# CPCIS_PWR_MOD_DC.net
KiCad netlist of a schematic drawn in Altium Designer
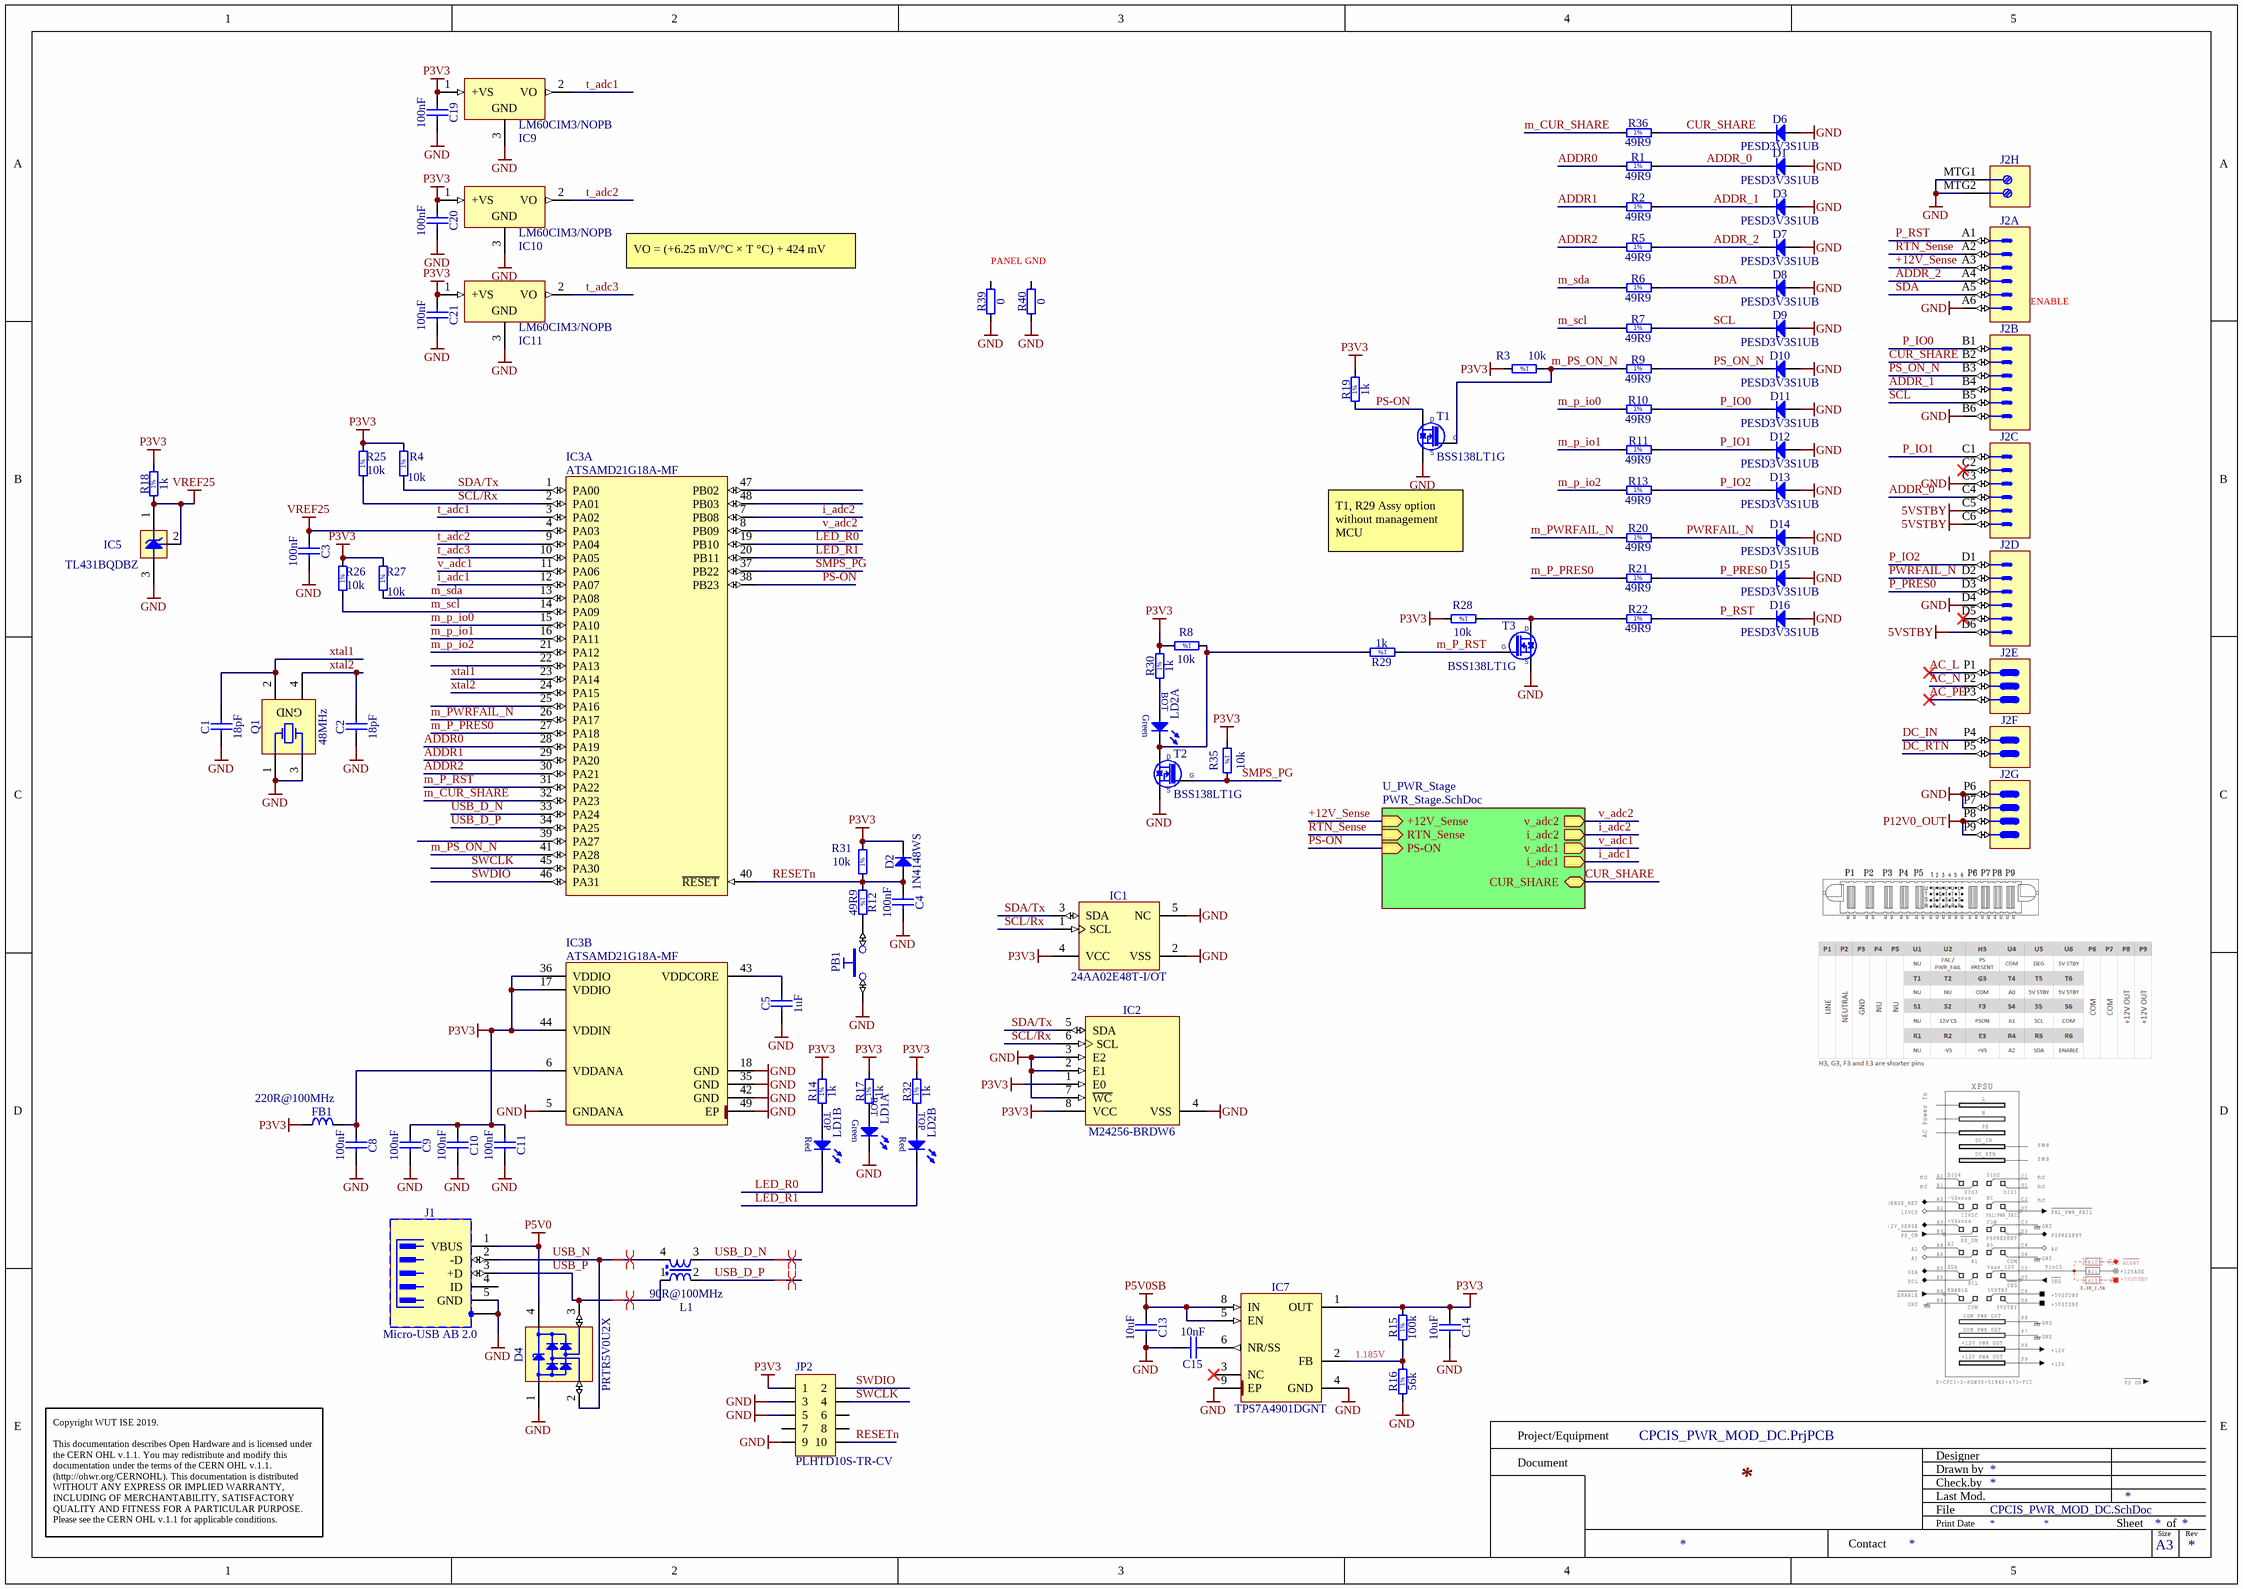
[diagram p0: CPCIS_PWR_MOD_DC.SchDoc]

(export (version "E")
  (design (tool "Eeschema 10.0.6"))
  (components
    (comp (ref "C1")
      (value "18pF")
      (footprint "CAPC1005X55N")
      (description "Non-polarised capacitor")
      (fields (field (name "PART NUMBER") "CC0402_18PF_50V_5%_C0G") (field (name "VOLTAGE") "50V"))
      (libsource (lib "Capacitors") (part "Capacitor - non polarized"))
    )
    (comp (ref "C2")
      (value "18pF")
      (footprint "CAPC1005X55N")
      (description "Non-polarised capacitor")
      (fields (field (name "PART NUMBER") "CC0402_18PF_50V_5%_C0G") (field (name "VOLTAGE") "50V"))
      (libsource (lib "Capacitors") (part "Capacitor - non polarized"))
    )
    (comp (ref "C3")
      (value "100nF")
      (footprint "CAPC1005X55N")
      (description "Non-polarised capacitor")
      (fields (field (name "PART NUMBER") "CC0402_100NF_16V_10%_X7R") (field (name "VOLTAGE") "16V"))
      (libsource (lib "Capacitors") (part "Capacitor - non polarized"))
    )
    (comp (ref "C4")
      (value "100nF")
      (footprint "CAPC1005X55N")
      (description "Non-polarised capacitor")
      (fields (field (name "PART NUMBER") "CC0402_100NF_16V_10%_X7R") (field (name "VOLTAGE") "16V"))
      (libsource (lib "Capacitors") (part "Capacitor - non polarized"))
    )
    (comp (ref "C5")
      (value "1uF")
      (footprint "CAPC1608X87N")
      (description "Non-polarised capacitor")
      (fields (field (name "PART NUMBER") "CC0603_1UF_16V_10%_X7R") (field (name "VOLTAGE") "16V"))
      (libsource (lib "Capacitors") (part "Capacitor - non polarized"))
    )
    (comp (ref "C8")
      (value "100nF")
      (footprint "CAPC1005X55N")
      (description "Non-polarised capacitor")
      (fields (field (name "PART NUMBER") "CC0402_100NF_16V_10%_X7R") (field (name "VOLTAGE") "16V"))
      (libsource (lib "Capacitors") (part "Capacitor - non polarized"))
    )
    (comp (ref "C9")
      (value "100nF")
      (footprint "CAPC1005X55N")
      (description "Non-polarised capacitor")
      (fields (field (name "PART NUMBER") "CC0402_100NF_16V_10%_X7R") (field (name "VOLTAGE") "16V"))
      (libsource (lib "Capacitors") (part "Capacitor - non polarized"))
    )
    (comp (ref "C10")
      (value "100nF")
      (footprint "CAPC1005X55N")
      (description "Non-polarised capacitor")
      (fields (field (name "PART NUMBER") "CC0402_100NF_16V_10%_X7R") (field (name "VOLTAGE") "16V"))
      (libsource (lib "Capacitors") (part "Capacitor - non polarized"))
    )
    (comp (ref "C11")
      (value "100nF")
      (footprint "CAPC1005X55N")
      (description "Non-polarised capacitor")
      (fields (field (name "PART NUMBER") "CC0402_100NF_16V_10%_X7R") (field (name "VOLTAGE") "16V"))
      (libsource (lib "Capacitors") (part "Capacitor - non polarized"))
    )
    (comp (ref "C13")
      (value "10uF")
      (footprint "CAPC2012X135N")
      (description "Non-polarised capacitor")
      (fields (field (name "PART NUMBER") "CC0805_10UF_16V_10%_X5R") (field (name "VOLTAGE") "16V"))
      (libsource (lib "Capacitors") (part "Capacitor - non polarized"))
    )
    (comp (ref "C14")
      (value "10uF")
      (footprint "CAPC2012X135N")
      (description "Non-polarised capacitor")
      (fields (field (name "PART NUMBER") "CC0805_10UF_16V_10%_X5R") (field (name "VOLTAGE") "16V"))
      (libsource (lib "Capacitors") (part "Capacitor - non polarized"))
    )
    (comp (ref "C15")
      (value "10nF")
      (footprint "CAPC1005X55N")
      (description "Non-polarised capacitor")
      (fields (field (name "PART NUMBER") "CC0402_10NF_50V_10%_X7R") (field (name "VOLTAGE") "50V"))
      (libsource (lib "Capacitors") (part "Capacitor - non polarized"))
    )
    (comp (ref "C19")
      (value "100nF")
      (footprint "CAPC1005X55N")
      (description "Non-polarised capacitor")
      (fields (field (name "PART NUMBER") "CC0402_100NF_16V_10%_X7R") (field (name "VOLTAGE") "16V"))
      (libsource (lib "Capacitors") (part "Capacitor - non polarized"))
    )
    (comp (ref "C20")
      (value "100nF")
      (footprint "CAPC1005X55N")
      (description "Non-polarised capacitor")
      (fields (field (name "PART NUMBER") "CC0402_100NF_16V_10%_X7R") (field (name "VOLTAGE") "16V"))
      (libsource (lib "Capacitors") (part "Capacitor - non polarized"))
    )
    (comp (ref "C21")
      (value "100nF")
      (footprint "CAPC1005X55N")
      (description "Non-polarised capacitor")
      (fields (field (name "PART NUMBER") "CC0402_100NF_16V_10%_X7R") (field (name "VOLTAGE") "16V"))
      (libsource (lib "Capacitors") (part "Capacitor - non polarized"))
    )
    (comp (ref "D1")
      (value "PESD3V3S1UB")
      (footprint "SODFL1608X65N")
      (description "ESD protection diode")
      (fields (field (name "VOLTAGE") "3V3") (field (name "POWER") "330W"))
      (libsource (lib "ICs And Semiconductors") (part "Diode ESD"))
    )
    (comp (ref "D2")
      (value "1N4148WS")
      (footprint "SODFL2512X100N")
      (description "Diode")
      (fields (field (name "VOLTAGE") "75V") (field (name "POWER") "150mA"))
      (libsource (lib "ICs And Semiconductors") (part "Diode"))
    )
    (comp (ref "D3")
      (value "PESD3V3S1UB")
      (footprint "SODFL1608X65N")
      (description "ESD protection diode")
      (fields (field (name "VOLTAGE") "3V3") (field (name "POWER") "330W"))
      (libsource (lib "ICs And Semiconductors") (part "Diode ESD"))
    )
    (comp (ref "D4")
      (value "PRTR5V0U2X")
      (footprint "SOT190P230X110-4N")
      (description "Ultra Low Capacitance Double Rail-to-Rail ESD Protection Diode")
      (fields (field (name "VOLTAGE") "5.5V") (field (name "MANUFACTURER") "NXP SEMICONDUCTORS"))
      (libsource (lib "ICs And Semiconductors") (part "PRTR5V0U2X"))
    )
    (comp (ref "D6")
      (value "PESD3V3S1UB")
      (footprint "SODFL1608X65N")
      (description "ESD protection diode")
      (fields (field (name "VOLTAGE") "3V3") (field (name "POWER") "330W"))
      (libsource (lib "ICs And Semiconductors") (part "Diode ESD"))
    )
    (comp (ref "D7")
      (value "PESD3V3S1UB")
      (footprint "SODFL1608X65N")
      (description "ESD protection diode")
      (fields (field (name "VOLTAGE") "3V3") (field (name "POWER") "330W"))
      (libsource (lib "ICs And Semiconductors") (part "Diode ESD"))
    )
    (comp (ref "D8")
      (value "PESD3V3S1UB")
      (footprint "SODFL1608X65N")
      (description "ESD protection diode")
      (fields (field (name "VOLTAGE") "3V3") (field (name "POWER") "330W"))
      (libsource (lib "ICs And Semiconductors") (part "Diode ESD"))
    )
    (comp (ref "D9")
      (value "PESD3V3S1UB")
      (footprint "SODFL1608X65N")
      (description "ESD protection diode")
      (fields (field (name "VOLTAGE") "3V3") (field (name "POWER") "330W"))
      (libsource (lib "ICs And Semiconductors") (part "Diode ESD"))
    )
    (comp (ref "D10")
      (value "PESD3V3S1UB")
      (footprint "SODFL1608X65N")
      (description "ESD protection diode")
      (fields (field (name "VOLTAGE") "3V3") (field (name "POWER") "330W"))
      (libsource (lib "ICs And Semiconductors") (part "Diode ESD"))
    )
    (comp (ref "D11")
      (value "PESD3V3S1UB")
      (footprint "SODFL1608X65N")
      (description "ESD protection diode")
      (fields (field (name "VOLTAGE") "3V3") (field (name "POWER") "330W"))
      (libsource (lib "ICs And Semiconductors") (part "Diode ESD"))
    )
    (comp (ref "D12")
      (value "PESD3V3S1UB")
      (footprint "SODFL1608X65N")
      (description "ESD protection diode")
      (fields (field (name "VOLTAGE") "3V3") (field (name "POWER") "330W"))
      (libsource (lib "ICs And Semiconductors") (part "Diode ESD"))
    )
    (comp (ref "D13")
      (value "PESD3V3S1UB")
      (footprint "SODFL1608X65N")
      (description "ESD protection diode")
      (fields (field (name "VOLTAGE") "3V3") (field (name "POWER") "330W"))
      (libsource (lib "ICs And Semiconductors") (part "Diode ESD"))
    )
    (comp (ref "D14")
      (value "PESD3V3S1UB")
      (footprint "SODFL1608X65N")
      (description "ESD protection diode")
      (fields (field (name "VOLTAGE") "3V3") (field (name "POWER") "330W"))
      (libsource (lib "ICs And Semiconductors") (part "Diode ESD"))
    )
    (comp (ref "D15")
      (value "PESD3V3S1UB")
      (footprint "SODFL1608X65N")
      (description "ESD protection diode")
      (fields (field (name "VOLTAGE") "3V3") (field (name "POWER") "330W"))
      (libsource (lib "ICs And Semiconductors") (part "Diode ESD"))
    )
    (comp (ref "D16")
      (value "PESD3V3S1UB")
      (footprint "SODFL1608X65N")
      (description "ESD protection diode")
      (fields (field (name "VOLTAGE") "3V3") (field (name "POWER") "330W"))
      (libsource (lib "ICs And Semiconductors") (part "Diode ESD"))
    )
    (comp (ref "FB1")
      (value "220R@100MHz")
      (footprint "INDC2012X105N")
      (description "Inductor")
      (fields (field (name "PART NUMBER") "IND0805_MURATA_BLM21PG221SN1D") (field (name "POWER") "2A"))
      (libsource (lib "Inductors & Transformers") (part "Inductor"))
    )
    (comp (ref "IC1")
      (value "24AA02E48T-I/OT")
      (footprint "SOT95P280X145-5N")
      (description "1.7V-5.5V, 2K I2C Serial EEPROM With EUI-48 Node Identity")
      (fields (field (name "MANUFACTURER") "MICROCHIP TECHNOLOGY"))
      (libsource (lib "ICs And Semiconductors") (part "24AA02E48T-I/OT"))
    )
    (comp (ref "IC2")
      (value "M24256-BRDW6")
      (footprint "SOP65P640X120-8N")
      (description "256-Kbit Serial I²C Bus EEPROM")
      (fields
        (field (name "PART NUMBER") "M24256-BRDW6P")
        (field (name "MANUFACTURER") "ST MICROELECTRONICS")
      )
      (libsource (lib "LIBRARY_SCH") (part "MEM_M24256-BRDW6P"))
    )
    (comp (ref "IC3")
      (value "ATSAMD21G18A-MF")
      (footprint "QFN50P700X700X100-49N-S525")
      (fields (field (name "MANUFACTURER") "MICROCHIP"))
      (libsource (lib "ICs And Semiconductors") (part "ATSAMD21G18A-MF"))
    )
    (comp (ref "IC5")
      (value "TL431BQDBZ")
      (footprint "SOT95P250X110-3N")
      (description "Precision Reference 1=Cathode 2=Adj 3=Anode")
      (fields (field (name "MANUFACTURER") "NXP SEMICONDUCTORS"))
      (libsource (lib "ICs And Semiconductors") (part "VREF 1C-2ADJ-3A"))
    )
    (comp (ref "IC7")
      (value "TPS7A4901DGNT")
      (footprint "SOP65P490X110-9N-R157X189")
      (description "+36V, +150mA, Ultralow-Noise, Positive Linear Regulator")
      (fields (field (name "MANUFACTURER") "TEXAS INSTRUMENTS"))
      (libsource (lib "ICs And Semiconductors") (part "TPS7A4901DGN"))
    )
    (comp (ref "IC9")
      (value "LM60CIM3/NOPB")
      (footprint "DBZ0003A_M")
      (description "2.7V Temperature Sensor, 3-pin SOT-23, Pb-Free")
      (fields (field (name "MANUFACTURER") "Texas Instruments"))
      (libsource (lib "Altium Content Vault") (part "SEN-TEMP-LM34AH-3"))
    )
    (comp (ref "IC10")
      (value "LM60CIM3/NOPB")
      (footprint "DBZ0003A_M")
      (description "2.7V Temperature Sensor, 3-pin SOT-23, Pb-Free")
      (fields (field (name "MANUFACTURER") "Texas Instruments"))
      (libsource (lib "Altium Content Vault") (part "SEN-TEMP-LM34AH-3"))
    )
    (comp (ref "IC11")
      (value "LM60CIM3/NOPB")
      (footprint "DBZ0003A_M")
      (description "2.7V Temperature Sensor, 3-pin SOT-23, Pb-Free")
      (fields (field (name "MANUFACTURER") "Texas Instruments"))
      (libsource (lib "Altium Content Vault") (part "SEN-TEMP-LM34AH-3"))
    )
    (comp (ref "J1")
      (value "Micro-USB AB 2.0")
      (footprint "HIROSE_ZX62RD-AB-5P8(30)")
      (description "5 Pin + 1 Shield USB Receptacle")
      (fields
        (field (name "PART NUMBER") "HIROSE_ZX62RD-AB-5P8(30)")
        (field (name "MANUFACTURER") "HIROSE (HRS)")
      )
      (libsource (lib "Connectors") (part "Connector USB 5 Pin + 1Shield"))
    )
    (comp (ref "J2")
      (value "PwrBlade")
      (footprint "AMPHENOL_51939-667")
      (description "Thru-Hole, Lead 3.43mm, PowerBlade Right Angled Power Connector 3ACP 2P 24S 4P Contacts")
      (fields (field (name "PART NUMBER") "AMPHENOL_51939-667") (field (name "MANUFACTURER") "AMPHENOL"))
      (libsource (lib "Connectors") (part "AMPHENOL_51939-667"))
    )
    (comp (ref "JP2")
      (value "PLHTD10S-TR-CV")
      (footprint "PLHTD10S-TR-CV")
      (description "1.27 mm dual row goldpin (Maritex)")
      (libsource (lib "LIBRARY_SCH") (part "CON_2x5 1.27 SMT Male"))
    )
    (comp (ref "L1")
      (value "90R@100MHz")
      (footprint "IND_MURATA_DLW21S")
      (description "Inductor Common Mode")
      (fields (field (name "PART NUMBER") "IND_MURATA_DLW21SN900SQ2L") (field (name "POWER") "330mA"))
      (libsource (lib "Inductors & Transformers") (part "Inductor Common Mode 1Dot-2 4Dot-3"))
    )
    (comp (ref "LD1")
      (value "Red/Green")
      (footprint "LED_DIALIGHT_571-0112F")
      (description "2x LED  Botom Green, Top Red")
      (fields (field (name "PART NUMBER") "LED_DIALIGHT_571-0112F") (field (name "MANUFACTURER") "DIALIGHT"))
      (libsource (lib "ICs And Semiconductors") (part "LED x2 G-1C2A-BOT_R-3C4A-TOP"))
    )
    (comp (ref "LD2")
      (value "Red/Green")
      (footprint "LED_DIALIGHT_571-0112F")
      (description "2x LED  Botom Green, Top Red")
      (fields (field (name "PART NUMBER") "LED_DIALIGHT_571-0112F") (field (name "MANUFACTURER") "DIALIGHT"))
      (libsource (lib "ICs And Semiconductors") (part "LED x2 G-1C2A-BOT_R-3C4A-TOP"))
    )
    (comp (ref "PB1")
      (value "Push Button")
      (footprint "PB_TYCO_FSMSM")
      (description "Push-Button Switch SPDT")
      (fields (field (name "PART NUMBER") "PB_TYCO_FSMSM") (field (name "MANUFACTURER") "TYCO ELECTRONICS"))
      (libsource (lib "Eletro-mechanical") (part "PB SPST 1NO-2NO"))
    )
    (comp (ref "Q1")
      (value "48MHz")
      (footprint "XTAL_TXC_7M")
      (description "Crystal 4 pins 1=XTAL Control 2=GND3=XTAL 4=GND")
      (fields
        (field (name "PART NUMBER") "XTAL_48MHZ_TXC_7M-48.000MAHV")
        (field (name "MANUFACTURER") "TXC CORPORATION")
      )
      (libsource (lib "ICs And Semiconductors") (part "Quartz Crystal 1X 2GND 3X 4GND"))
    )
    (comp (ref "R1")
      (value "49R9")
      (footprint "RESC1005X40N")
      (description "Resistor - 1%")
      (fields (field (name "PART NUMBER") "R0402_49R9_1%_0.0625W_100PPM") (field (name "POWER") "0.0625W"))
      (libsource (lib "Resistors") (part "Resistor - 1%"))
    )
    (comp (ref "R2")
      (value "49R9")
      (footprint "RESC1005X40N")
      (description "Resistor - 1%")
      (fields (field (name "PART NUMBER") "R0402_49R9_1%_0.0625W_100PPM") (field (name "POWER") "0.0625W"))
      (libsource (lib "Resistors") (part "Resistor - 1%"))
    )
    (comp (ref "R3")
      (value "10k")
      (footprint "RESC1005X40N")
      (description "Resistor - 1%")
      (fields (field (name "PART NUMBER") "R0402_10K_1%_0.0625W_100PPM") (field (name "POWER") "0.0625W"))
      (libsource (lib "Resistors") (part "Resistor - 1%"))
    )
    (comp (ref "R4")
      (value "10k")
      (footprint "RESC1005X40N")
      (description "Resistor - 1%")
      (fields (field (name "PART NUMBER") "R0402_10K_1%_0.0625W_100PPM") (field (name "POWER") "0.0625W"))
      (libsource (lib "Resistors") (part "Resistor - 1%"))
    )
    (comp (ref "R5")
      (value "49R9")
      (footprint "RESC1005X40N")
      (description "Resistor - 1%")
      (fields (field (name "PART NUMBER") "R0402_49R9_1%_0.0625W_100PPM") (field (name "POWER") "0.0625W"))
      (libsource (lib "Resistors") (part "Resistor - 1%"))
    )
    (comp (ref "R6")
      (value "49R9")
      (footprint "RESC1005X40N")
      (description "Resistor - 1%")
      (fields (field (name "PART NUMBER") "R0402_49R9_1%_0.0625W_100PPM") (field (name "POWER") "0.0625W"))
      (libsource (lib "Resistors") (part "Resistor - 1%"))
    )
    (comp (ref "R7")
      (value "49R9")
      (footprint "RESC1005X40N")
      (description "Resistor - 1%")
      (fields (field (name "PART NUMBER") "R0402_49R9_1%_0.0625W_100PPM") (field (name "POWER") "0.0625W"))
      (libsource (lib "Resistors") (part "Resistor - 1%"))
    )
    (comp (ref "R8")
      (value "10k")
      (footprint "RESC1005X40N")
      (description "Resistor - 1%")
      (fields (field (name "PART NUMBER") "R0402_10K_1%_0.0625W_100PPM") (field (name "POWER") "0.0625W"))
      (libsource (lib "Resistors") (part "Resistor - 1%"))
    )
    (comp (ref "R9")
      (value "49R9")
      (footprint "RESC1005X40N")
      (description "Resistor - 1%")
      (fields (field (name "PART NUMBER") "R0402_49R9_1%_0.0625W_100PPM") (field (name "POWER") "0.0625W"))
      (libsource (lib "Resistors") (part "Resistor - 1%"))
    )
    (comp (ref "R10")
      (value "49R9")
      (footprint "RESC1005X40N")
      (description "Resistor - 1%")
      (fields (field (name "PART NUMBER") "R0402_49R9_1%_0.0625W_100PPM") (field (name "POWER") "0.0625W"))
      (libsource (lib "Resistors") (part "Resistor - 1%"))
    )
    (comp (ref "R11")
      (value "49R9")
      (footprint "RESC1005X40N")
      (description "Resistor - 1%")
      (fields (field (name "PART NUMBER") "R0402_49R9_1%_0.0625W_100PPM") (field (name "POWER") "0.0625W"))
      (libsource (lib "Resistors") (part "Resistor - 1%"))
    )
    (comp (ref "R12")
      (value "49R9")
      (footprint "RESC1005X40N")
      (description "Resistor - 1%")
      (fields (field (name "PART NUMBER") "R0402_49R9_1%_0.0625W_100PPM") (field (name "POWER") "0.0625W"))
      (libsource (lib "Resistors") (part "Resistor - 1%"))
    )
    (comp (ref "R13")
      (value "49R9")
      (footprint "RESC1005X40N")
      (description "Resistor - 1%")
      (fields (field (name "PART NUMBER") "R0402_49R9_1%_0.0625W_100PPM") (field (name "POWER") "0.0625W"))
      (libsource (lib "Resistors") (part "Resistor - 1%"))
    )
    (comp (ref "R14")
      (value "1k")
      (footprint "RESC1005X40N")
      (description "Resistor - 1%")
      (fields (field (name "PART NUMBER") "R0402_1K_1%_0.0625W_100PPM") (field (name "POWER") "0.0625W"))
      (libsource (lib "Resistors") (part "Resistor - 1%"))
    )
    (comp (ref "R15")
      (value "100k")
      (footprint "RESC1005X40N")
      (description "Resistor - 1%")
      (fields (field (name "PART NUMBER") "R0402_100K_1%_0.0625W_100PPM") (field (name "POWER") "0.0625W"))
      (libsource (lib "Resistors") (part "Resistor - 1%"))
    )
    (comp (ref "R16")
      (value "56k")
      (footprint "RESC1005X40N")
      (description "Resistor - 1%")
      (fields (field (name "PART NUMBER") "R0402_56K_1%_0.0625W_100PPM") (field (name "POWER") "0.0625W"))
      (libsource (lib "Resistors") (part "Resistor - 1%"))
    )
    (comp (ref "R17")
      (value "1k")
      (footprint "RESC1005X40N")
      (description "Resistor - 1%")
      (fields (field (name "PART NUMBER") "R0402_1K_1%_0.0625W_100PPM") (field (name "POWER") "0.0625W"))
      (libsource (lib "Resistors") (part "Resistor - 1%"))
    )
    (comp (ref "R18")
      (value "1k")
      (footprint "RESC1005X40N")
      (description "Resistor - 1%")
      (fields (field (name "PART NUMBER") "R0402_1K_1%_0.0625W_100PPM") (field (name "POWER") "0.0625W"))
      (libsource (lib "Resistors") (part "Resistor - 1%"))
    )
    (comp (ref "R19")
      (value "1k")
      (footprint "RESC1005X40N")
      (description "Resistor - 1%")
      (fields (field (name "PART NUMBER") "R0402_1K_1%_0.0625W_100PPM") (field (name "POWER") "0.0625W"))
      (libsource (lib "Resistors") (part "Resistor - 1%"))
    )
    (comp (ref "R20")
      (value "49R9")
      (footprint "RESC1005X40N")
      (description "Resistor - 1%")
      (fields (field (name "PART NUMBER") "R0402_49R9_1%_0.0625W_100PPM") (field (name "POWER") "0.0625W"))
      (libsource (lib "Resistors") (part "Resistor - 1%"))
    )
    (comp (ref "R21")
      (value "49R9")
      (footprint "RESC1005X40N")
      (description "Resistor - 1%")
      (fields (field (name "PART NUMBER") "R0402_49R9_1%_0.0625W_100PPM") (field (name "POWER") "0.0625W"))
      (libsource (lib "Resistors") (part "Resistor - 1%"))
    )
    (comp (ref "R22")
      (value "49R9")
      (footprint "RESC1005X40N")
      (description "Resistor - 1%")
      (fields (field (name "PART NUMBER") "R0402_49R9_1%_0.0625W_100PPM") (field (name "POWER") "0.0625W"))
      (libsource (lib "Resistors") (part "Resistor - 1%"))
    )
    (comp (ref "R25")
      (value "10k")
      (footprint "RESC1005X40N")
      (description "Resistor - 1%")
      (fields (field (name "PART NUMBER") "R0402_10K_1%_0.0625W_100PPM") (field (name "POWER") "0.0625W"))
      (libsource (lib "Resistors") (part "Resistor - 1%"))
    )
    (comp (ref "R26")
      (value "10k")
      (footprint "RESC1005X40N")
      (description "Resistor - 1%")
      (fields (field (name "PART NUMBER") "R0402_10K_1%_0.0625W_100PPM") (field (name "POWER") "0.0625W"))
      (libsource (lib "Resistors") (part "Resistor - 1%"))
    )
    (comp (ref "R27")
      (value "10k")
      (footprint "RESC1005X40N")
      (description "Resistor - 1%")
      (fields (field (name "PART NUMBER") "R0402_10K_1%_0.0625W_100PPM") (field (name "POWER") "0.0625W"))
      (libsource (lib "Resistors") (part "Resistor - 1%"))
    )
    (comp (ref "R28")
      (value "10k")
      (footprint "RESC1005X40N")
      (description "Resistor - 1%")
      (fields (field (name "PART NUMBER") "R0402_10K_1%_0.0625W_100PPM") (field (name "POWER") "0.0625W"))
      (libsource (lib "Resistors") (part "Resistor - 1%"))
    )
    (comp (ref "R29")
      (value "1k")
      (footprint "RESC1005X40N")
      (description "Resistor - 1%")
      (fields (field (name "PART NUMBER") "R0402_1K_1%_0.0625W_100PPM") (field (name "POWER") "0.0625W"))
      (libsource (lib "Resistors") (part "Resistor - 1%"))
    )
    (comp (ref "R30")
      (value "1k")
      (footprint "RESC1005X40N")
      (description "Resistor - 1%")
      (fields (field (name "PART NUMBER") "R0402_1K_1%_0.0625W_100PPM") (field (name "POWER") "0.0625W"))
      (libsource (lib "Resistors") (part "Resistor - 1%"))
    )
    (comp (ref "R31")
      (value "10k")
      (footprint "RESC1005X40N")
      (description "Resistor - 1%")
      (fields (field (name "PART NUMBER") "R0402_10K_1%_0.0625W_100PPM") (field (name "POWER") "0.0625W"))
      (libsource (lib "Resistors") (part "Resistor - 1%"))
    )
    (comp (ref "R32")
      (value "1k")
      (footprint "RESC1005X40N")
      (description "Resistor - 1%")
      (fields (field (name "PART NUMBER") "R0402_1K_1%_0.0625W_100PPM") (field (name "POWER") "0.0625W"))
      (libsource (lib "Resistors") (part "Resistor - 1%"))
    )
    (comp (ref "R35")
      (value "10k")
      (footprint "RESC1005X40N")
      (description "Resistor - 1%")
      (fields (field (name "PART NUMBER") "R0402_10K_1%_0.0625W_100PPM") (field (name "POWER") "0.0625W"))
      (libsource (lib "Resistors") (part "Resistor - 1%"))
    )
    (comp (ref "R36")
      (value "49R9")
      (footprint "RESC1005X40N")
      (description "Resistor - 1%")
      (fields (field (name "PART NUMBER") "R0402_49R9_1%_0.0625W_100PPM") (field (name "POWER") "0.0625W"))
      (libsource (lib "Resistors") (part "Resistor - 1%"))
    )
    (comp (ref "R39")
      (value "0")
      (footprint "RESC1608X55N")
      (description "Resistor")
      (fields (field (name "PART NUMBER") "R0603_0R_JUMPER") (field (name "MANUFACTURER") "GENERIC"))
      (libsource (lib "Resistors") (part "Resistor"))
    )
    (comp (ref "R40")
      (value "0")
      (footprint "RESC1608X55N")
      (description "Resistor")
      (fields (field (name "PART NUMBER") "R0603_0R_JUMPER") (field (name "MANUFACTURER") "GENERIC"))
      (libsource (lib "Resistors") (part "Resistor"))
    )
    (comp (ref "T1")
      (value "BSS138LT1G")
      (footprint "SOT95P240X110-3N")
      (description "N-CHANNEL MOSFET WITH DIODE")
      (fields (field (name "MANUFACTURER") "ON SEMICONDUCTOR"))
      (libsource (lib "ICs And Semiconductors") (part "N-MOSFET-D 1G 2S 3D"))
    )
    (comp (ref "T2")
      (value "BSS138LT1G")
      (footprint "SOT95P240X110-3N")
      (description "N-CHANNEL MOSFET WITH DIODE")
      (fields (field (name "MANUFACTURER") "ON SEMICONDUCTOR"))
      (libsource (lib "ICs And Semiconductors") (part "N-MOSFET-D 1G 2S 3D"))
    )
    (comp (ref "T3")
      (value "BSS138LT1G")
      (footprint "SOT95P240X110-3N")
      (description "N-CHANNEL MOSFET WITH DIODE")
      (fields (field (name "MANUFACTURER") "ON SEMICONDUCTOR"))
      (libsource (lib "") (part "N-MOSFET-D 1G 2S 3D_1"))
    )
  )
  (nets
    (net (code "1") (name "/+12V_Sense") (class "Default")
      (node (ref "J2") (pin "A3") (pinfunction "A3_A3") (pintype "bidirectional"))
    )
    (net (code "2") (name "/AC_L") (class "Default")
      (node (ref "J2") (pin "P1") (pinfunction "P1_P1") (pintype "bidirectional+no_connect"))
    )
    (net (code "3") (name "/AC_N") (class "Default")
      (node (ref "J2") (pin "P2") (pinfunction "P2_P2") (pintype "bidirectional"))
    )
    (net (code "4") (name "/AC_PE") (class "Default")
      (node (ref "J2") (pin "P3") (pinfunction "P3_P3") (pintype "bidirectional+no_connect"))
    )
    (net (code "5") (name "/ADDR0") (class "Default")
      (node (ref "IC3") (pin "28") (pinfunction "PA19_28") (pintype "bidirectional"))
      (node (ref "R1") (pin "1") (pinfunction "1_1") (pintype "passive"))
    )
    (net (code "6") (name "/ADDR1") (class "Default")
      (node (ref "IC3") (pin "29") (pinfunction "PA20_29") (pintype "bidirectional"))
      (node (ref "R2") (pin "1") (pinfunction "1_1") (pintype "passive"))
    )
    (net (code "7") (name "/ADDR2") (class "Default")
      (node (ref "IC3") (pin "30") (pinfunction "PA21_30") (pintype "bidirectional"))
      (node (ref "R5") (pin "1") (pinfunction "1_1") (pintype "passive"))
    )
    (net (code "8") (name "/ADDR_0") (class "Default")
      (node (ref "D1") (pin "1") (pinfunction "C_1") (pintype "passive"))
      (node (ref "J2") (pin "C4") (pinfunction "C4_C4") (pintype "bidirectional"))
      (node (ref "R1") (pin "2") (pinfunction "2_2") (pintype "passive"))
    )
    (net (code "9") (name "/ADDR_1") (class "Default")
      (node (ref "D3") (pin "1") (pinfunction "C_1") (pintype "passive"))
      (node (ref "J2") (pin "B4") (pinfunction "B4_B4") (pintype "bidirectional"))
      (node (ref "R2") (pin "2") (pinfunction "2_2") (pintype "passive"))
    )
    (net (code "10") (name "/ADDR_2") (class "Default")
      (node (ref "D7") (pin "1") (pinfunction "C_1") (pintype "passive"))
      (node (ref "J2") (pin "A4") (pinfunction "A4_A4") (pintype "bidirectional"))
      (node (ref "R5") (pin "2") (pinfunction "2_2") (pintype "passive"))
    )
    (net (code "11") (name "/CUR_SHARE") (class "Default")
      (node (ref "D6") (pin "1") (pinfunction "C_1") (pintype "passive"))
      (node (ref "J2") (pin "B2") (pinfunction "B2_B2") (pintype "bidirectional"))
      (node (ref "R36") (pin "2") (pinfunction "2_2") (pintype "passive"))
    )
    (net (code "12") (name "/DC_IN") (class "Default")
      (node (ref "J2") (pin "P4") (pinfunction "P4_P4") (pintype "bidirectional"))
    )
    (net (code "13") (name "/DC_RTN") (class "Default")
      (node (ref "J2") (pin "P5") (pinfunction "P5_P5") (pintype "bidirectional"))
    )
    (net (code "14") (name "/LED_R0") (class "Default")
      (node (ref "IC3") (pin "19") (pinfunction "PB10_19") (pintype "bidirectional"))
      (node (ref "LD1") (pin "3") (pinfunction "C_3") (pintype "passive"))
    )
    (net (code "15") (name "/LED_R1") (class "Default")
      (node (ref "IC3") (pin "20") (pinfunction "PB11_20") (pintype "bidirectional"))
      (node (ref "LD2") (pin "3") (pinfunction "C_3") (pintype "passive"))
    )
    (net (code "16") (name "/PS-ON") (class "Default")
      (node (ref "IC3") (pin "38") (pinfunction "PB23_38") (pintype "bidirectional"))
      (node (ref "R19") (pin "1") (pinfunction "1_1") (pintype "passive"))
      (node (ref "T1") (pin "3") (pinfunction "D_3") (pintype "passive"))
    )
    (net (code "17") (name "/PS_ON_N") (class "Default")
      (node (ref "D10") (pin "1") (pinfunction "C_1") (pintype "passive"))
      (node (ref "J2") (pin "B3") (pinfunction "B3_B3") (pintype "bidirectional"))
      (node (ref "R9") (pin "2") (pinfunction "2_2") (pintype "passive"))
    )
    (net (code "18") (name "/PWRFAIL_N") (class "Default")
      (node (ref "D14") (pin "1") (pinfunction "C_1") (pintype "passive"))
      (node (ref "J2") (pin "D2") (pinfunction "D2_D2") (pintype "bidirectional"))
      (node (ref "R20") (pin "2") (pinfunction "2_2") (pintype "passive"))
    )
    (net (code "19") (name "/P_IO0") (class "Default")
      (node (ref "D11") (pin "1") (pinfunction "C_1") (pintype "passive"))
      (node (ref "J2") (pin "B1") (pinfunction "B1_B1") (pintype "bidirectional"))
      (node (ref "R10") (pin "2") (pinfunction "2_2") (pintype "passive"))
    )
    (net (code "20") (name "/P_IO1") (class "Default")
      (node (ref "D12") (pin "1") (pinfunction "C_1") (pintype "passive"))
      (node (ref "J2") (pin "C1") (pinfunction "C1_C1") (pintype "bidirectional"))
      (node (ref "R11") (pin "2") (pinfunction "2_2") (pintype "passive"))
    )
    (net (code "21") (name "/P_IO2") (class "Default")
      (node (ref "D13") (pin "1") (pinfunction "C_1") (pintype "passive"))
      (node (ref "J2") (pin "D1") (pinfunction "D1_D1") (pintype "bidirectional"))
      (node (ref "R13") (pin "2") (pinfunction "2_2") (pintype "passive"))
    )
    (net (code "22") (name "/P_PRES0") (class "Default")
      (node (ref "D15") (pin "1") (pinfunction "C_1") (pintype "passive"))
      (node (ref "J2") (pin "D3") (pinfunction "D3_D3") (pintype "bidirectional"))
      (node (ref "R21") (pin "2") (pinfunction "2_2") (pintype "passive"))
    )
    (net (code "23") (name "/P_RST") (class "Default")
      (node (ref "D16") (pin "1") (pinfunction "C_1") (pintype "passive"))
      (node (ref "J2") (pin "A1") (pinfunction "A1_A1") (pintype "bidirectional"))
      (node (ref "R22") (pin "2") (pinfunction "2_2") (pintype "passive"))
    )
    (net (code "24") (name "/RESETn") (class "Default")
      (node (ref "C4") (pin "1") (pinfunction "1_1") (pintype "passive"))
      (node (ref "D2") (pin "2") (pinfunction "A_2") (pintype "passive"))
      (node (ref "IC3") (pin "40") (pinfunction "~{RESET}_40") (pintype "input"))
      (node (ref "JP2") (pin "10") (pinfunction "10_10") (pintype "passive"))
      (node (ref "R12") (pin "1") (pinfunction "1_1") (pintype "passive"))
      (node (ref "R31") (pin "1") (pinfunction "1_1") (pintype "passive"))
    )
    (net (code "25") (name "/RTN_Sense") (class "Default")
      (node (ref "J2") (pin "A2") (pinfunction "A2_A2") (pintype "bidirectional"))
    )
    (net (code "26") (name "/SCL") (class "Default")
      (node (ref "D9") (pin "1") (pinfunction "C_1") (pintype "passive"))
      (node (ref "J2") (pin "B5") (pinfunction "B5_B5") (pintype "bidirectional"))
      (node (ref "R7") (pin "2") (pinfunction "2_2") (pintype "passive"))
    )
    (net (code "27") (name "/SCL{slash}Rx") (class "Default")
      (node (ref "IC1") (pin "1") (pinfunction "SCL_1") (pintype "input"))
      (node (ref "IC2") (pin "6") (pinfunction "SCL_6") (pintype "input"))
      (node (ref "IC3") (pin "2") (pinfunction "PA01_2") (pintype "bidirectional"))
      (node (ref "R25") (pin "1") (pinfunction "1_1") (pintype "passive"))
    )
    (net (code "28") (name "/SDA") (class "Default")
      (node (ref "D8") (pin "1") (pinfunction "C_1") (pintype "passive"))
      (node (ref "J2") (pin "A5") (pinfunction "A5_A5") (pintype "bidirectional"))
      (node (ref "R6") (pin "2") (pinfunction "2_2") (pintype "passive"))
    )
    (net (code "29") (name "/SDA{slash}Tx") (class "Default")
      (node (ref "IC1") (pin "3") (pinfunction "SDA_3") (pintype "bidirectional"))
      (node (ref "IC2") (pin "5") (pinfunction "SDA_5") (pintype "bidirectional"))
      (node (ref "IC3") (pin "1") (pinfunction "PA00_1") (pintype "bidirectional"))
      (node (ref "R4") (pin "1") (pinfunction "1_1") (pintype "passive"))
    )
    (net (code "30") (name "/SMPS_PG") (class "Default")
      (node (ref "IC3") (pin "37") (pinfunction "PB22_37") (pintype "bidirectional"))
      (node (ref "R35") (pin "2") (pinfunction "2_2") (pintype "passive"))
      (node (ref "T2") (pin "1") (pinfunction "G_1") (pintype "passive"))
    )
    (net (code "31") (name "/SWCLK") (class "Default")
      (node (ref "IC3") (pin "45") (pinfunction "PA30_45") (pintype "bidirectional"))
      (node (ref "JP2") (pin "4") (pinfunction "4_4") (pintype "passive"))
    )
    (net (code "32") (name "/SWDIO") (class "Default")
      (node (ref "IC3") (pin "46") (pinfunction "PA31_46") (pintype "bidirectional"))
      (node (ref "JP2") (pin "2") (pinfunction "2_2") (pintype "passive"))
    )
    (net (code "33") (name "/USB_D_N") (class "Default")
      (node (ref "IC3") (pin "33") (pinfunction "PA24_33") (pintype "bidirectional"))
      (node (ref "L1") (pin "3") (pinfunction "3_3") (pintype "passive"))
    )
    (net (code "34") (name "/USB_D_P") (class "Default")
      (node (ref "IC3") (pin "34") (pinfunction "PA25_34") (pintype "bidirectional"))
      (node (ref "L1") (pin "2") (pinfunction "2_2") (pintype "passive"))
    )
    (net (code "35") (name "/USB_N") (class "Default")
      (node (ref "D4") (pin "2") (pinfunction "I/O1_2") (pintype "bidirectional"))
      (node (ref "J1") (pin "2") (pinfunction "-D_2") (pintype "bidirectional"))
      (node (ref "L1") (pin "4") (pinfunction "4_4") (pintype "passive"))
    )
    (net (code "36") (name "/USB_P") (class "Default")
      (node (ref "D4") (pin "3") (pinfunction "I/O2_3") (pintype "bidirectional"))
      (node (ref "J1") (pin "3") (pinfunction "+D_3") (pintype "bidirectional"))
      (node (ref "L1") (pin "1") (pinfunction "1_1") (pintype "passive"))
    )
    (net (code "37") (name "/i_adc1") (class "Default")
      (node (ref "IC3") (pin "12") (pinfunction "PA07_12") (pintype "bidirectional"))
    )
    (net (code "38") (name "/i_adc2") (class "Default")
      (node (ref "IC3") (pin "7") (pinfunction "PB08_7") (pintype "bidirectional"))
    )
    (net (code "39") (name "/m_CUR_SHARE") (class "Default")
      (node (ref "IC3") (pin "32") (pinfunction "PA23_32") (pintype "bidirectional"))
      (node (ref "R36") (pin "1") (pinfunction "1_1") (pintype "passive"))
    )
    (net (code "40") (name "/m_PS_ON_N") (class "Default")
      (node (ref "IC3") (pin "41") (pinfunction "PA28_41") (pintype "bidirectional"))
      (node (ref "R3") (pin "1") (pinfunction "1_1") (pintype "passive"))
      (node (ref "R9") (pin "1") (pinfunction "1_1") (pintype "passive"))
      (node (ref "T1") (pin "1") (pinfunction "G_1") (pintype "passive"))
    )
    (net (code "41") (name "/m_PWRFAIL_N") (class "Default")
      (node (ref "IC3") (pin "26") (pinfunction "PA17_26") (pintype "bidirectional"))
      (node (ref "R20") (pin "1") (pinfunction "1_1") (pintype "passive"))
    )
    (net (code "42") (name "/m_P_PRES0") (class "Default")
      (node (ref "IC3") (pin "27") (pinfunction "PA18_27") (pintype "bidirectional"))
      (node (ref "R21") (pin "1") (pinfunction "1_1") (pintype "passive"))
    )
    (net (code "43") (name "/m_P_RST") (class "Default")
      (node (ref "IC3") (pin "31") (pinfunction "PA22_31") (pintype "bidirectional"))
      (node (ref "R29") (pin "1") (pinfunction "1_1") (pintype "passive"))
      (node (ref "T3") (pin "1") (pinfunction "G_1") (pintype "passive"))
    )
    (net (code "44") (name "/m_p_io0") (class "Default")
      (node (ref "IC3") (pin "15") (pinfunction "PA10_15") (pintype "bidirectional"))
      (node (ref "R10") (pin "1") (pinfunction "1_1") (pintype "passive"))
    )
    (net (code "45") (name "/m_p_io1") (class "Default")
      (node (ref "IC3") (pin "16") (pinfunction "PA11_16") (pintype "bidirectional"))
      (node (ref "R11") (pin "1") (pinfunction "1_1") (pintype "passive"))
    )
    (net (code "46") (name "/m_p_io2") (class "Default")
      (node (ref "IC3") (pin "21") (pinfunction "PA12_21") (pintype "bidirectional"))
      (node (ref "R13") (pin "1") (pinfunction "1_1") (pintype "passive"))
    )
    (net (code "47") (name "/m_scl") (class "Default")
      (node (ref "IC3") (pin "14") (pinfunction "PA09_14") (pintype "bidirectional"))
      (node (ref "R26") (pin "1") (pinfunction "1_1") (pintype "passive"))
      (node (ref "R7") (pin "1") (pinfunction "1_1") (pintype "passive"))
    )
    (net (code "48") (name "/m_sda") (class "Default")
      (node (ref "IC3") (pin "13") (pinfunction "PA08_13") (pintype "bidirectional"))
      (node (ref "R27") (pin "1") (pinfunction "1_1") (pintype "passive"))
      (node (ref "R6") (pin "1") (pinfunction "1_1") (pintype "passive"))
    )
    (net (code "49") (name "/t_adc1") (class "Default")
      (node (ref "IC3") (pin "3") (pinfunction "PA02_3") (pintype "bidirectional"))
      (node (ref "IC9") (pin "2") (pinfunction "VO_2") (pintype "output"))
    )
    (net (code "50") (name "/t_adc2") (class "Default")
      (node (ref "IC10") (pin "2") (pinfunction "VO_2") (pintype "output"))
      (node (ref "IC3") (pin "9") (pinfunction "PA04_9") (pintype "bidirectional"))
    )
    (net (code "51") (name "/t_adc3") (class "Default")
      (node (ref "IC11") (pin "2") (pinfunction "VO_2") (pintype "output"))
      (node (ref "IC3") (pin "10") (pinfunction "PA05_10") (pintype "bidirectional"))
    )
    (net (code "52") (name "/v_adc1") (class "Default")
      (node (ref "IC3") (pin "11") (pinfunction "PA06_11") (pintype "bidirectional"))
    )
    (net (code "53") (name "/v_adc2") (class "Default")
      (node (ref "IC3") (pin "8") (pinfunction "PB09_8") (pintype "bidirectional"))
    )
    (net (code "54") (name "/xtal1") (class "Default")
      (node (ref "C1") (pin "2") (pinfunction "2_2") (pintype "passive"))
      (node (ref "IC3") (pin "23") (pinfunction "PA14_23") (pintype "bidirectional"))
      (node (ref "Q1") (pin "2") (pinfunction "GND_2") (pintype "power_in"))
    )
    (net (code "55") (name "/xtal2") (class "Default")
      (node (ref "C2") (pin "2") (pinfunction "2_2") (pintype "passive"))
      (node (ref "IC3") (pin "24") (pinfunction "PA15_24") (pintype "bidirectional"))
      (node (ref "Q1") (pin "4") (pinfunction "GND_4") (pintype "power_in"))
    )
    (net (code "56") (name "5VSTBY") (class "Default")
      (node (ref "J2") (pin "C5") (pinfunction "C5_C5") (pintype "bidirectional"))
      (node (ref "J2") (pin "C6") (pinfunction "C6_C6") (pintype "bidirectional"))
      (node (ref "J2") (pin "D6") (pinfunction "D6_D6") (pintype "bidirectional"))
    )
    (net (code "57") (name "GND") (class "Default")
      (node (ref "C1") (pin "1") (pinfunction "1_1") (pintype "passive"))
      (node (ref "C10") (pin "2") (pinfunction "2_2") (pintype "passive"))
      (node (ref "C11") (pin "2") (pinfunction "2_2") (pintype "passive"))
      (node (ref "C13") (pin "2") (pinfunction "2_2") (pintype "passive"))
      (node (ref "C14") (pin "2") (pinfunction "2_2") (pintype "passive"))
      (node (ref "C15") (pin "2") (pinfunction "2_2") (pintype "passive"))
      (node (ref "C19") (pin "2") (pinfunction "2_2") (pintype "passive"))
      (node (ref "C2") (pin "1") (pinfunction "1_1") (pintype "passive"))
      (node (ref "C20") (pin "2") (pinfunction "2_2") (pintype "passive"))
      (node (ref "C21") (pin "2") (pinfunction "2_2") (pintype "passive"))
      (node (ref "C3") (pin "2") (pinfunction "2_2") (pintype "passive"))
      (node (ref "C4") (pin "2") (pinfunction "2_2") (pintype "passive"))
      (node (ref "C5") (pin "1") (pinfunction "1_1") (pintype "passive"))
      (node (ref "C8") (pin "2") (pinfunction "2_2") (pintype "passive"))
      (node (ref "C9") (pin "2") (pinfunction "2_2") (pintype "passive"))
      (node (ref "D1") (pin "2") (pinfunction "A_2") (pintype "passive"))
      (node (ref "D10") (pin "2") (pinfunction "A_2") (pintype "passive"))
      (node (ref "D11") (pin "2") (pinfunction "A_2") (pintype "passive"))
      (node (ref "D12") (pin "2") (pinfunction "A_2") (pintype "passive"))
      (node (ref "D13") (pin "2") (pinfunction "A_2") (pintype "passive"))
      (node (ref "D14") (pin "2") (pinfunction "A_2") (pintype "passive"))
      (node (ref "D15") (pin "2") (pinfunction "A_2") (pintype "passive"))
      (node (ref "D16") (pin "2") (pinfunction "A_2") (pintype "passive"))
      (node (ref "D3") (pin "2") (pinfunction "A_2") (pintype "passive"))
      (node (ref "D4") (pin "1") (pinfunction "GND_1") (pintype "power_in"))
      (node (ref "D6") (pin "2") (pinfunction "A_2") (pintype "passive"))
      (node (ref "D7") (pin "2") (pinfunction "A_2") (pintype "passive"))
      (node (ref "D8") (pin "2") (pinfunction "A_2") (pintype "passive"))
      (node (ref "D9") (pin "2") (pinfunction "A_2") (pintype "passive"))
      (node (ref "IC1") (pin "2") (pinfunction "VSS_2") (pintype "power_in"))
      (node (ref "IC1") (pin "5") (pinfunction "NC_5") (pintype "passive"))
      (node (ref "IC10") (pin "3") (pinfunction "GND_3") (pintype "power_in"))
      (node (ref "IC11") (pin "3") (pinfunction "GND_3") (pintype "power_in"))
      (node (ref "IC2") (pin "2") (pinfunction "E1_2") (pintype "input"))
      (node (ref "IC2") (pin "3") (pinfunction "E2_3") (pintype "input"))
      (node (ref "IC2") (pin "4") (pinfunction "VSS_4") (pintype "power_in"))
      (node (ref "IC2") (pin "7") (pinfunction "~{WC}_7") (pintype "input"))
      (node (ref "IC3") (pin "18") (pinfunction "GND_18") (pintype "power_in"))
      (node (ref "IC3") (pin "35") (pinfunction "GND_35") (pintype "power_in"))
      (node (ref "IC3") (pin "42") (pinfunction "GND_42") (pintype "power_in"))
      (node (ref "IC3") (pin "49") (pinfunction "EP_49") (pintype "passive"))
      (node (ref "IC3") (pin "5") (pinfunction "GNDANA_5") (pintype "power_in"))
      (node (ref "IC5") (pin "3") (pinfunction "A_3") (pintype "passive"))
      (node (ref "IC7") (pin "4") (pinfunction "GND_4") (pintype "power_in"))
      (node (ref "IC7") (pin "9") (pinfunction "EP_9") (pintype "power_in"))
      (node (ref "IC9") (pin "3") (pinfunction "GND_3") (pintype "power_in"))
      (node (ref "J1") (pin "5") (pinfunction "GND_5") (pintype "power_in"))
      (node (ref "J1") (pin "6") (pinfunction "SH_6") (pintype "power_in"))
      (node (ref "J2") (pin "A6") (pinfunction "A6_A6") (pintype "bidirectional"))
      (node (ref "J2") (pin "B6") (pinfunction "B6_B6") (pintype "bidirectional"))
      (node (ref "J2") (pin "C3") (pinfunction "C3_C3") (pintype "bidirectional"))
      (node (ref "J2") (pin "D4") (pinfunction "D4_D4") (pintype "bidirectional"))
      (node (ref "J2") (pin "MTG1") (pinfunction "MTG1_MTG1") (pintype "passive"))
      (node (ref "J2") (pin "MTG2") (pinfunction "MTG2_MTG2") (pintype "passive"))
      (node (ref "J2") (pin "P6") (pinfunction "P6_P6") (pintype "bidirectional"))
      (node (ref "J2") (pin "P7") (pinfunction "P7_P7") (pintype "bidirectional"))
      (node (ref "JP2") (pin "3") (pinfunction "3_3") (pintype "passive"))
      (node (ref "JP2") (pin "5") (pinfunction "5_5") (pintype "passive"))
      (node (ref "JP2") (pin "9") (pinfunction "9_9") (pintype "passive"))
      (node (ref "LD1") (pin "1") (pinfunction "C_1") (pintype "passive"))
      (node (ref "PB1") (pin "1") (pinfunction "1_1") (pintype "bidirectional"))
      (node (ref "Q1") (pin "1") (pinfunction "X_1") (pintype "passive"))
      (node (ref "Q1") (pin "3") (pinfunction "X_3") (pintype "passive"))
      (node (ref "R16") (pin "1") (pinfunction "1_1") (pintype "passive"))
      (node (ref "R39") (pin "1") (pinfunction "1_1") (pintype "passive"))
      (node (ref "R40") (pin "1") (pinfunction "1_1") (pintype "passive"))
      (node (ref "T1") (pin "2") (pinfunction "S_2") (pintype "passive"))
      (node (ref "T2") (pin "2") (pinfunction "S_2") (pintype "passive"))
      (node (ref "T3") (pin "2") (pinfunction "S_2") (pintype "passive"))
    )
    (net (code "58") (name "Net-(IC3B-VDDANA)") (class "Default")
      (node (ref "C8") (pin "1") (pinfunction "1_1") (pintype "passive"))
      (node (ref "FB1") (pin "2") (pinfunction "2_2") (pintype "passive"))
      (node (ref "IC3") (pin "6") (pinfunction "VDDANA_6") (pintype "power_in"))
    )
    (net (code "59") (name "Net-(IC3B-VDDCORE)") (class "Default")
      (node (ref "C5") (pin "2") (pinfunction "2_2") (pintype "passive"))
      (node (ref "IC3") (pin "43") (pinfunction "VDDCORE_43") (pintype "power_in"))
    )
    (net (code "60") (name "Net-(IC7-FB)") (class "Default")
      (node (ref "IC7") (pin "2") (pinfunction "FB_2") (pintype "passive"))
      (node (ref "R15") (pin "1") (pinfunction "1_1") (pintype "passive"))
      (node (ref "R16") (pin "2") (pinfunction "2_2") (pintype "passive"))
    )
    (net (code "61") (name "Net-(IC7-NR{slash}SS)") (class "Default")
      (node (ref "C15") (pin "1") (pinfunction "1_1") (pintype "passive"))
      (node (ref "IC7") (pin "6") (pinfunction "NR/SS_6") (pintype "output"))
    )
    (net (code "62") (name "Net-(LD1A-A)") (class "Default")
      (node (ref "LD1") (pin "2") (pinfunction "A_2") (pintype "passive"))
      (node (ref "R17") (pin "1") (pinfunction "1_1") (pintype "passive"))
    )
    (net (code "63") (name "Net-(LD1B-A)") (class "Default")
      (node (ref "LD1") (pin "4") (pinfunction "A_4") (pintype "passive"))
      (node (ref "R14") (pin "1") (pinfunction "1_1") (pintype "passive"))
    )
    (net (code "64") (name "Net-(LD2A-A)") (class "Default")
      (node (ref "LD2") (pin "2") (pinfunction "A_2") (pintype "passive"))
      (node (ref "R30") (pin "1") (pinfunction "1_1") (pintype "passive"))
    )
    (net (code "65") (name "Net-(LD2A-C)") (class "Default")
      (node (ref "LD2") (pin "1") (pinfunction "C_1") (pintype "passive"))
      (node (ref "R29") (pin "2") (pinfunction "2_2") (pintype "passive"))
      (node (ref "R8") (pin "1") (pinfunction "1_1") (pintype "passive"))
      (node (ref "T2") (pin "3") (pinfunction "D_3") (pintype "passive"))
    )
    (net (code "66") (name "Net-(LD2B-A)") (class "Default")
      (node (ref "LD2") (pin "4") (pinfunction "A_4") (pintype "passive"))
      (node (ref "R32") (pin "1") (pinfunction "1_1") (pintype "passive"))
    )
    (net (code "67") (name "Net-(PB1-Pad2)") (class "Default")
      (node (ref "PB1") (pin "2") (pinfunction "2_2") (pintype "bidirectional"))
      (node (ref "R12") (pin "2") (pinfunction "2_2") (pintype "passive"))
    )
    (net (code "68") (name "Net-(T3-D)") (class "Default")
      (node (ref "R22") (pin "1") (pinfunction "1_1") (pintype "passive"))
      (node (ref "R28") (pin "1") (pinfunction "1_1") (pintype "passive"))
      (node (ref "T3") (pin "3") (pinfunction "D_3") (pintype "passive"))
    )
    (net (code "69") (name "P3V3") (class "Default")
      (node (ref "C10") (pin "1") (pinfunction "1_1") (pintype "passive"))
      (node (ref "C11") (pin "1") (pinfunction "1_1") (pintype "passive"))
      (node (ref "C14") (pin "1") (pinfunction "1_1") (pintype "passive"))
      (node (ref "C19") (pin "1") (pinfunction "1_1") (pintype "passive"))
      (node (ref "C20") (pin "1") (pinfunction "1_1") (pintype "passive"))
      (node (ref "C21") (pin "1") (pinfunction "1_1") (pintype "passive"))
      (node (ref "C9") (pin "1") (pinfunction "1_1") (pintype "passive"))
      (node (ref "D2") (pin "1") (pinfunction "C_1") (pintype "passive"))
      (node (ref "FB1") (pin "1") (pinfunction "1_1") (pintype "passive"))
      (node (ref "IC1") (pin "4") (pinfunction "VCC_4") (pintype "power_in"))
      (node (ref "IC10") (pin "1") (pinfunction "+VS_1") (pintype "input"))
      (node (ref "IC11") (pin "1") (pinfunction "+VS_1") (pintype "input"))
      (node (ref "IC2") (pin "1") (pinfunction "E0_1") (pintype "input"))
      (node (ref "IC2") (pin "8") (pinfunction "VCC_8") (pintype "power_in"))
      (node (ref "IC3") (pin "17") (pinfunction "VDDIO_17") (pintype "power_in"))
      (node (ref "IC3") (pin "36") (pinfunction "VDDIO_36") (pintype "power_in"))
      (node (ref "IC3") (pin "44") (pinfunction "VDDIN_44") (pintype "power_in"))
      (node (ref "IC7") (pin "1") (pinfunction "OUT_1") (pintype "power_in"))
      (node (ref "IC9") (pin "1") (pinfunction "+VS_1") (pintype "input"))
      (node (ref "JP2") (pin "1") (pinfunction "1_1") (pintype "passive"))
      (node (ref "R14") (pin "2") (pinfunction "2_2") (pintype "passive"))
      (node (ref "R15") (pin "2") (pinfunction "2_2") (pintype "passive"))
      (node (ref "R17") (pin "2") (pinfunction "2_2") (pintype "passive"))
      (node (ref "R18") (pin "2") (pinfunction "2_2") (pintype "passive"))
      (node (ref "R19") (pin "2") (pinfunction "2_2") (pintype "passive"))
      (node (ref "R25") (pin "2") (pinfunction "2_2") (pintype "passive"))
      (node (ref "R26") (pin "2") (pinfunction "2_2") (pintype "passive"))
      (node (ref "R27") (pin "2") (pinfunction "2_2") (pintype "passive"))
      (node (ref "R28") (pin "2") (pinfunction "2_2") (pintype "passive"))
      (node (ref "R3") (pin "2") (pinfunction "2_2") (pintype "passive"))
      (node (ref "R30") (pin "2") (pinfunction "2_2") (pintype "passive"))
      (node (ref "R31") (pin "2") (pinfunction "2_2") (pintype "passive"))
      (node (ref "R32") (pin "2") (pinfunction "2_2") (pintype "passive"))
      (node (ref "R35") (pin "1") (pinfunction "1_1") (pintype "passive"))
      (node (ref "R4") (pin "2") (pinfunction "2_2") (pintype "passive"))
      (node (ref "R8") (pin "2") (pinfunction "2_2") (pintype "passive"))
    )
    (net (code "70") (name "P5V0") (class "Default")
      (node (ref "D4") (pin "4") (pinfunction "VCC_4") (pintype "power_in"))
      (node (ref "J1") (pin "1") (pinfunction "VBUS_1") (pintype "power_in"))
    )
    (net (code "71") (name "P5V0SB") (class "Default")
      (node (ref "C13") (pin "1") (pinfunction "1_1") (pintype "passive"))
      (node (ref "IC7") (pin "5") (pinfunction "EN_5") (pintype "input"))
      (node (ref "IC7") (pin "8") (pinfunction "IN_8") (pintype "input"))
    )
    (net (code "72") (name "P12V0_OUT") (class "Default")
      (node (ref "J2") (pin "P8") (pinfunction "P8_P8") (pintype "bidirectional"))
      (node (ref "J2") (pin "P9") (pinfunction "P9_P9") (pintype "bidirectional"))
    )
    (net (code "73") (name "VREF25") (class "Default")
      (node (ref "C3") (pin "1") (pinfunction "1_1") (pintype "passive"))
      (node (ref "IC3") (pin "4") (pinfunction "PA03_4") (pintype "bidirectional"))
      (node (ref "IC5") (pin "1") (pinfunction "C_1") (pintype "passive"))
      (node (ref "IC5") (pin "2") (pinfunction "Adj_2") (pintype "passive"))
      (node (ref "R18") (pin "1") (pinfunction "1_1") (pintype "passive"))
    )
    (net (code "74") (name "unconnected-(IC3A-PA13-Pad22)") (class "Default")
      (node (ref "IC3") (pin "22") (pinfunction "PA13_22") (pintype "bidirectional"))
    )
    (net (code "75") (name "unconnected-(IC3A-PA16-Pad25)") (class "Default")
      (node (ref "IC3") (pin "25") (pinfunction "PA16_25") (pintype "bidirectional"))
    )
    (net (code "76") (name "unconnected-(IC3A-PA27-Pad39)") (class "Default")
      (node (ref "IC3") (pin "39") (pinfunction "PA27_39") (pintype "bidirectional"))
    )
    (net (code "77") (name "unconnected-(IC3A-PB02-Pad47)") (class "Default")
      (node (ref "IC3") (pin "47") (pinfunction "PB02_47") (pintype "bidirectional"))
    )
    (net (code "78") (name "unconnected-(IC3A-PB03-Pad48)") (class "Default")
      (node (ref "IC3") (pin "48") (pinfunction "PB03_48") (pintype "bidirectional"))
    )
    (net (code "79") (name "unconnected-(IC7-NC-Pad3)") (class "Default")
      (node (ref "IC7") (pin "3") (pinfunction "NC_3") (pintype "passive+no_connect"))
    )
    (net (code "80") (name "unconnected-(J1-ID-Pad4)") (class "Default")
      (node (ref "J1") (pin "4") (pinfunction "ID_4") (pintype "passive"))
    )
    (net (code "81") (name "unconnected-(J2-PadC2)") (class "Default")
      (node (ref "J2") (pin "C2") (pinfunction "C2_C2") (pintype "bidirectional+no_connect"))
    )
    (net (code "82") (name "unconnected-(J2-PadD5)") (class "Default")
      (node (ref "J2") (pin "D5") (pinfunction "D5_D5") (pintype "bidirectional+no_connect"))
    )
    (net (code "83") (name "unconnected-(JP2-Pad6)") (class "Default")
      (node (ref "JP2") (pin "6") (pinfunction "6_6") (pintype "passive"))
    )
    (net (code "84") (name "unconnected-(JP2-Pad7)") (class "Default")
      (node (ref "JP2") (pin "7") (pinfunction "7_7") (pintype "passive"))
    )
    (net (code "85") (name "unconnected-(JP2-Pad8)") (class "Default")
      (node (ref "JP2") (pin "8") (pinfunction "8_8") (pintype "passive"))
    )
    (net (code "86") (name "unconnected-(R39-Pad2)") (class "Default")
      (node (ref "R39") (pin "2") (pinfunction "2_2") (pintype "passive"))
    )
    (net (code "87") (name "unconnected-(R40-Pad2)") (class "Default")
      (node (ref "R40") (pin "2") (pinfunction "2_2") (pintype "passive"))
    )
  )
)
